# Linelance_Schematic_page3.net
KiCad netlist of a schematic drawn in Altium Designer
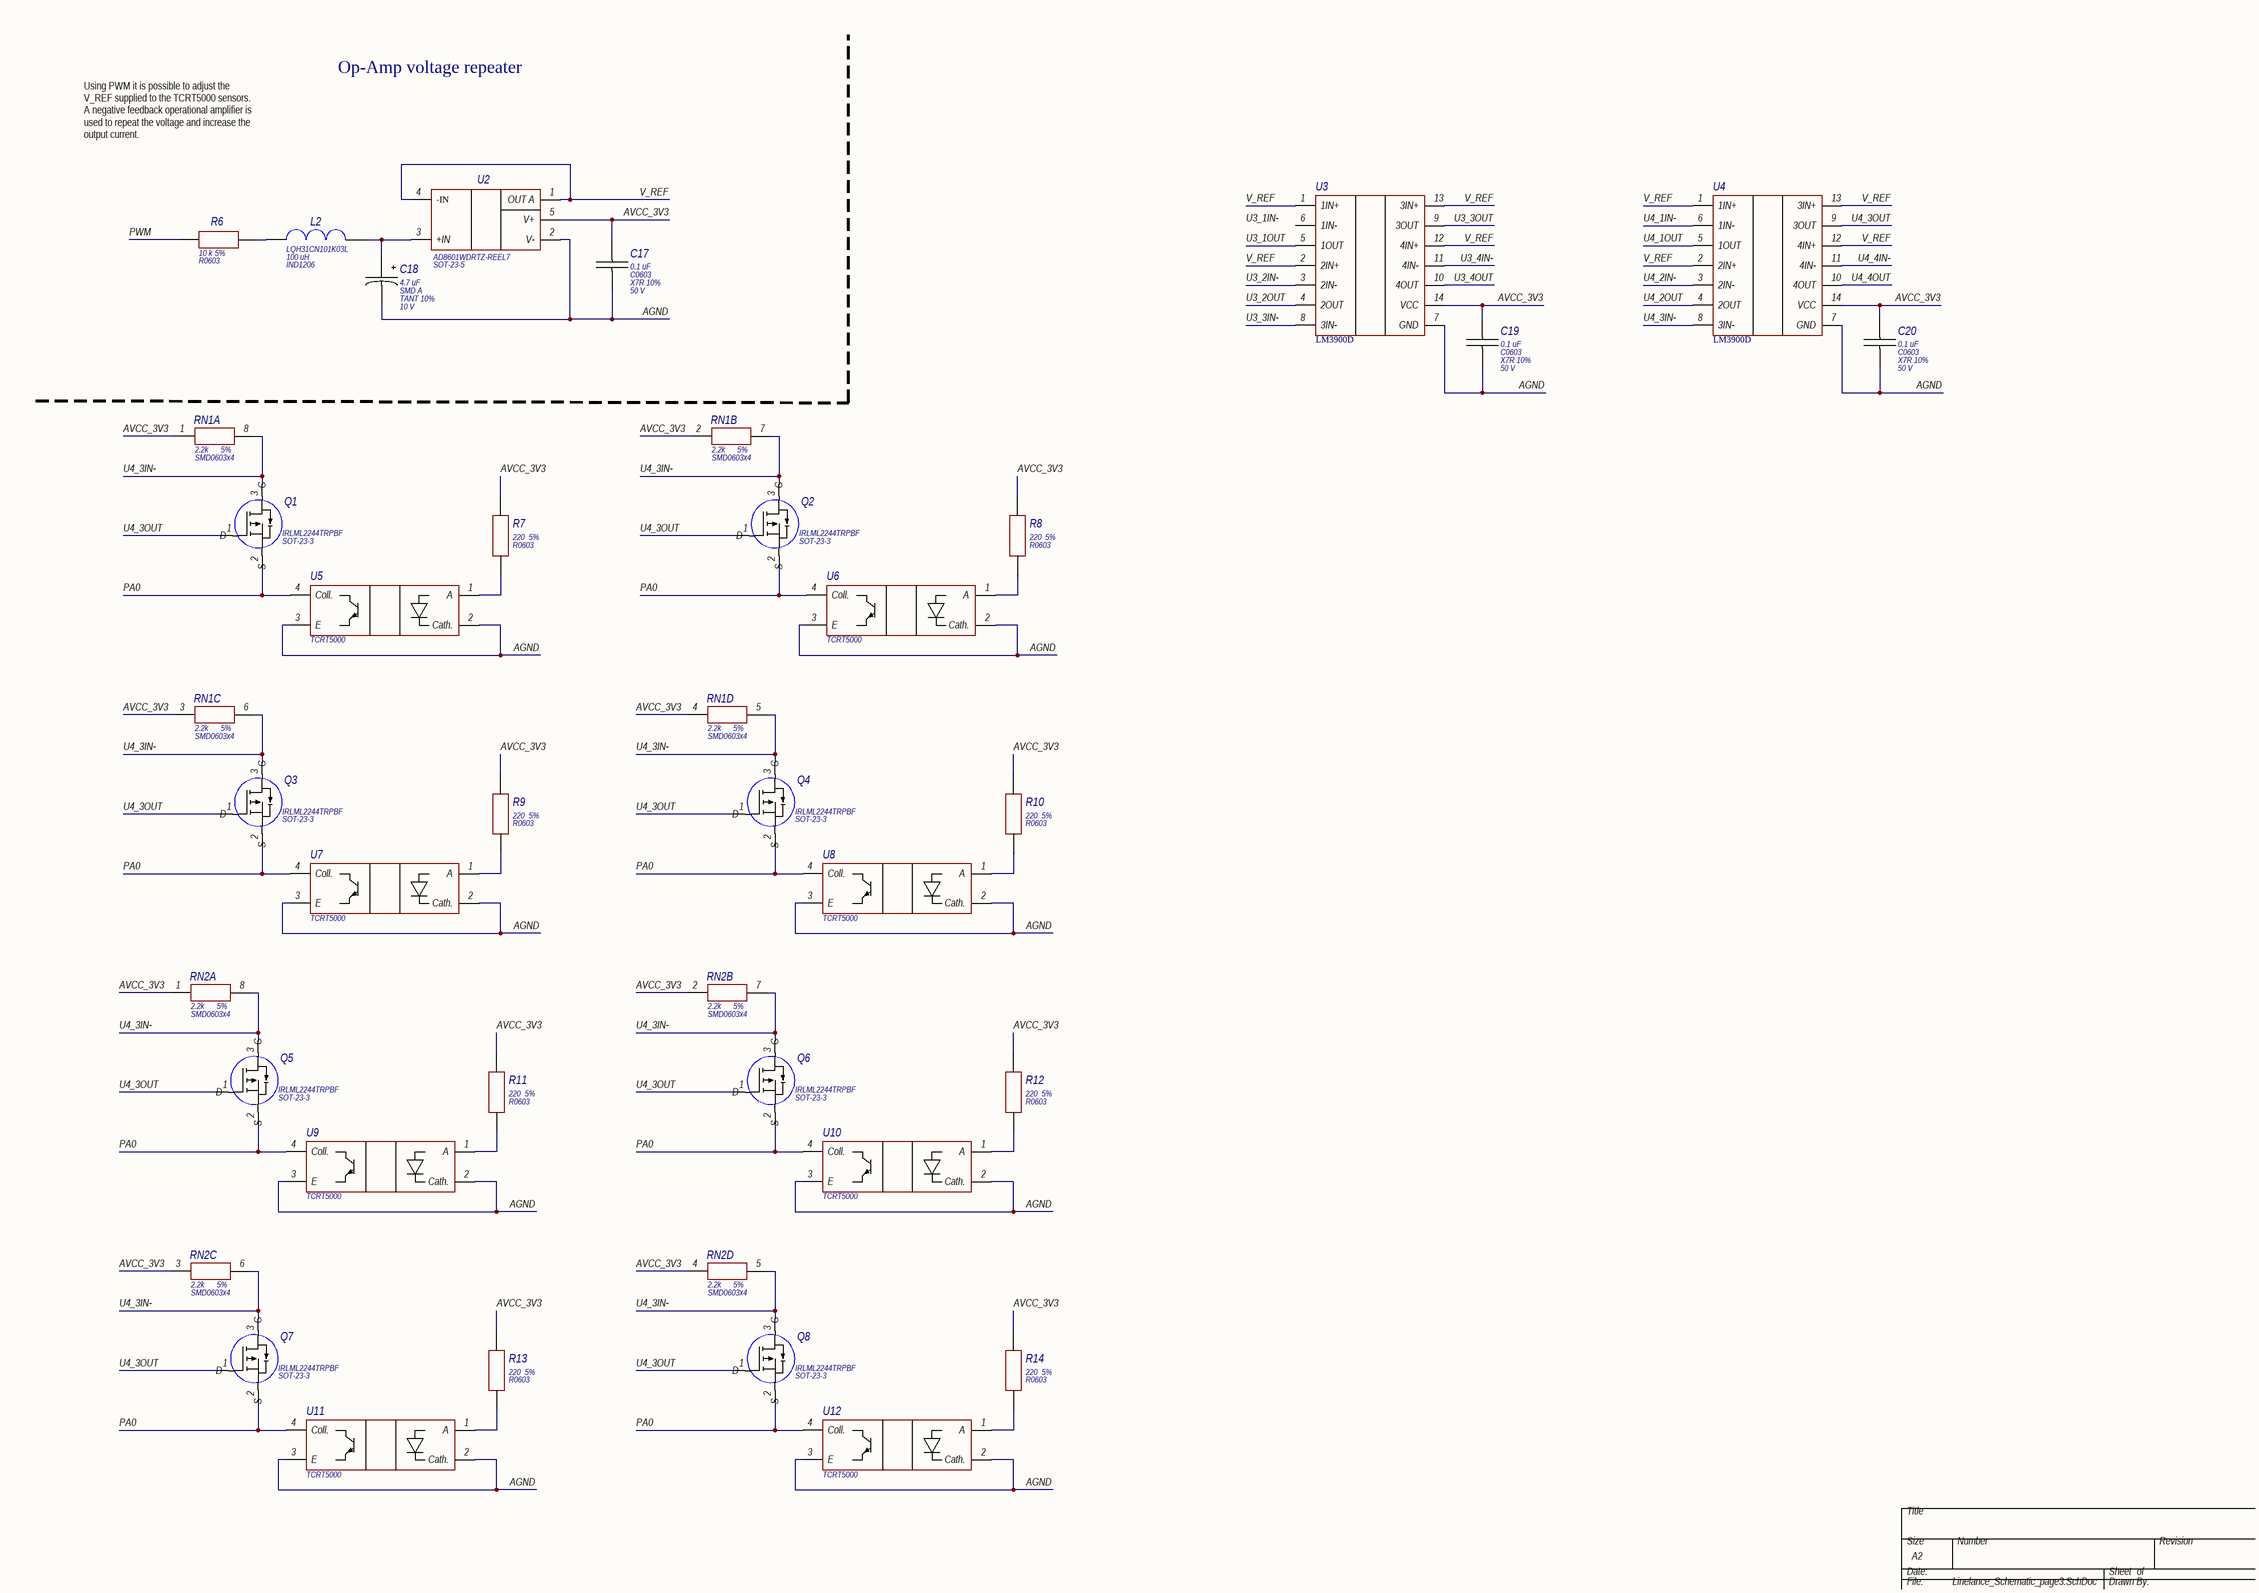
[diagram p0: Linelance_Schematic_page3.SchDoc]

(export (version "E")
  (design (tool "Eeschema 10.0.6"))
  (components
    (comp (ref "C17")
      (value "0.1 uF")
      (footprint "C0603")
      (fields
        (field (name "CASE") "C0603")
        (field (name "MANUFACTURER") "Murata Manufacturing")
        (field (name "MODEL") "X7R 10%")
        (field (name "VOLTAGE") "50 V")
      )
      (libsource (lib "Linelance_lib") (part "Capasitor_ceramic"))
    )
    (comp (ref "C18")
      (value "4.7 uF")
      (footprint "TANT-A")
      (fields
        (field (name "CASE") "SMD A")
        (field (name "MANUFACTURER") "China")
        (field (name "MODEL") "TANT 10%")
        (field (name "VOLTAGE") "10 V")
      )
      (libsource (lib "Linelance_lib") (part "Capasitor_tantalum"))
    )
    (comp (ref "C19")
      (value "0.1 uF")
      (footprint "C0603")
      (fields
        (field (name "CASE") "C0603")
        (field (name "MANUFACTURER") "Murata Manufacturing")
        (field (name "MODEL") "X7R 10%")
        (field (name "VOLTAGE") "50 V")
      )
      (libsource (lib "Linelance_lib") (part "Capasitor_ceramic"))
    )
    (comp (ref "C20")
      (value "0.1 uF")
      (footprint "C0603")
      (fields
        (field (name "CASE") "C0603")
        (field (name "MANUFACTURER") "Murata Manufacturing")
        (field (name "MODEL") "X7R 10%")
        (field (name "VOLTAGE") "50 V")
      )
      (libsource (lib "Linelance_lib") (part "Capasitor_ceramic"))
    )
    (comp (ref "L2")
      (value "100 uH")
      (footprint "IND1206")
      (fields
        (field (name "MODEL") "LQH31CN101K03L")
        (field (name "MANUFACTURER") "Murata Manufacturing")
        (field (name "CASE") "IND1206")
      )
      (libsource (lib "Linelance_lib") (part "Inductivity"))
    )
    (comp (ref "Q1")
      (value "IRLML2244TRPBF")
      (footprint "SOT-23-3")
      (description "MOSFET P-CH 20V 4.3A SOT23")
      (fields (field (name "CASE") "SOT-23-3") (field (name "MODEL") "IRLML2244TRPBF"))
      (libsource (lib "Linelance_lib") (part "IRLML2244TRPBF"))
    )
    (comp (ref "Q2")
      (value "IRLML2244TRPBF")
      (footprint "SOT-23-3")
      (description "MOSFET P-CH 20V 4.3A SOT23")
      (fields (field (name "CASE") "SOT-23-3") (field (name "MODEL") "IRLML2244TRPBF"))
      (libsource (lib "Linelance_lib") (part "IRLML2244TRPBF"))
    )
    (comp (ref "Q3")
      (value "IRLML2244TRPBF")
      (footprint "SOT-23-3")
      (description "MOSFET P-CH 20V 4.3A SOT23")
      (fields (field (name "CASE") "SOT-23-3") (field (name "MODEL") "IRLML2244TRPBF"))
      (libsource (lib "Linelance_lib") (part "IRLML2244TRPBF"))
    )
    (comp (ref "Q4")
      (value "IRLML2244TRPBF")
      (footprint "SOT-23-3")
      (description "MOSFET P-CH 20V 4.3A SOT23")
      (fields (field (name "CASE") "SOT-23-3") (field (name "MODEL") "IRLML2244TRPBF"))
      (libsource (lib "Linelance_lib") (part "IRLML2244TRPBF"))
    )
    (comp (ref "Q5")
      (value "IRLML2244TRPBF")
      (footprint "SOT-23-3")
      (description "MOSFET P-CH 20V 4.3A SOT23")
      (fields (field (name "CASE") "SOT-23-3") (field (name "MODEL") "IRLML2244TRPBF"))
      (libsource (lib "Linelance_lib") (part "IRLML2244TRPBF"))
    )
    (comp (ref "Q6")
      (value "IRLML2244TRPBF")
      (footprint "SOT-23-3")
      (description "MOSFET P-CH 20V 4.3A SOT23")
      (fields (field (name "CASE") "SOT-23-3") (field (name "MODEL") "IRLML2244TRPBF"))
      (libsource (lib "Linelance_lib") (part "IRLML2244TRPBF"))
    )
    (comp (ref "Q7")
      (value "IRLML2244TRPBF")
      (footprint "SOT-23-3")
      (description "MOSFET P-CH 20V 4.3A SOT23")
      (fields (field (name "CASE") "SOT-23-3") (field (name "MODEL") "IRLML2244TRPBF"))
      (libsource (lib "Linelance_lib") (part "IRLML2244TRPBF"))
    )
    (comp (ref "Q8")
      (value "IRLML2244TRPBF")
      (footprint "SOT-23-3")
      (description "MOSFET P-CH 20V 4.3A SOT23")
      (fields (field (name "CASE") "SOT-23-3") (field (name "MODEL") "IRLML2244TRPBF"))
      (libsource (lib "Linelance_lib") (part "IRLML2244TRPBF"))
    )
    (comp (ref "R6")
      (value "10 k")
      (footprint "R0603")
      (description "Rext.")
      (fields (field (name "MODEL") "5%") (field (name "CASE") "R0603"))
      (libsource (lib "") (part "Resistor_1"))
    )
    (comp (ref "R7")
      (value "220")
      (footprint "R0603")
      (description "Rext.")
      (fields (field (name "MODEL") "5%") (field (name "CASE") "R0603"))
      (libsource (lib "Linelance_lib") (part "Resistor"))
    )
    (comp (ref "R8")
      (value "220")
      (footprint "R0603")
      (description "Rext.")
      (fields (field (name "MODEL") "5%") (field (name "CASE") "R0603"))
      (libsource (lib "Linelance_lib") (part "Resistor"))
    )
    (comp (ref "R9")
      (value "220")
      (footprint "R0603")
      (description "Rext.")
      (fields (field (name "MODEL") "5%") (field (name "CASE") "R0603"))
      (libsource (lib "Linelance_lib") (part "Resistor"))
    )
    (comp (ref "R10")
      (value "220")
      (footprint "R0603")
      (description "Rext.")
      (fields (field (name "MODEL") "5%") (field (name "CASE") "R0603"))
      (libsource (lib "Linelance_lib") (part "Resistor"))
    )
    (comp (ref "R11")
      (value "220")
      (footprint "R0603")
      (description "Rext.")
      (fields (field (name "MODEL") "5%") (field (name "CASE") "R0603"))
      (libsource (lib "Linelance_lib") (part "Resistor"))
    )
    (comp (ref "R12")
      (value "220")
      (footprint "R0603")
      (description "Rext.")
      (fields (field (name "MODEL") "5%") (field (name "CASE") "R0603"))
      (libsource (lib "Linelance_lib") (part "Resistor"))
    )
    (comp (ref "R13")
      (value "220")
      (footprint "R0603")
      (description "Rext.")
      (fields (field (name "MODEL") "5%") (field (name "CASE") "R0603"))
      (libsource (lib "Linelance_lib") (part "Resistor"))
    )
    (comp (ref "R14")
      (value "220")
      (footprint "R0603")
      (description "Rext.")
      (fields (field (name "MODEL") "5%") (field (name "CASE") "R0603"))
      (libsource (lib "Linelance_lib") (part "Resistor"))
    )
    (comp (ref "RN1")
      (value "2.2k")
      (footprint "RN_YC164-JR-072K2L")
      (fields
        (field (name "MODEL") "5%")
        (field (name "CASE") "SMD0603x4")
        (field (name "MANUFACTURER") "Bourns")
      )
      (libsource (lib "Linelance_lib") (part "Resistor Network"))
    )
    (comp (ref "RN2")
      (value "2.2k")
      (footprint "RN_YC164-JR-072K2L")
      (fields
        (field (name "MODEL") "5%")
        (field (name "CASE") "SMD0603x4")
        (field (name "MANUFACTURER") "Bourns")
      )
      (libsource (lib "Linelance_lib") (part "Resistor Network"))
    )
    (comp (ref "U2")
      (value "AD8601WDRTZ-REEL7")
      (footprint "SOT-23-5")
      (description "IC OPAMP GP 1 CIRCUIT SOT23-5")
      (fields
        (field (name "MODEL") "AD8601WDRTZ-REEL7")
        (field (name "MANUFACTURER") "Analog Devices Inc.")
        (field (name "CASE") "SOT-23-5")
      )
      (libsource (lib "Linelance_lib") (part "AD8601"))
    )
    (comp (ref "U3")
      (value "LM3900D")
      (footprint "SOIC-14")
      (description "IC OPAMP GP 4 CIRCUIT 14SOIC")
      (fields (field (name "MANUFACTURER") "Texas Instruments"))
      (libsource (lib "Linelance_lib") (part "LM3900"))
    )
    (comp (ref "U4")
      (value "LM3900D")
      (footprint "SOIC-14")
      (description "IC OPAMP GP 4 CIRCUIT 14SOIC")
      (fields (field (name "MANUFACTURER") "Texas Instruments"))
      (libsource (lib "Linelance_lib") (part "LM3900"))
    )
    (comp (ref "U5")
      (value "TCRT5000")
      (footprint "TCRT5000")
      (description "SENSOR OPTO TRANS 15MM REFL PCB")
      (fields
        (field (name "MODEL") "TCRT5000")
        (field (name "MANUFACTURER") "Vishay Semiconductor Opto Division")
      )
      (libsource (lib "Linelance_lib") (part "TCRT5000"))
    )
    (comp (ref "U6")
      (value "TCRT5000")
      (footprint "TCRT5000")
      (description "SENSOR OPTO TRANS 15MM REFL PCB")
      (fields
        (field (name "MODEL") "TCRT5000")
        (field (name "MANUFACTURER") "Vishay Semiconductor Opto Division")
      )
      (libsource (lib "Linelance_lib") (part "TCRT5000"))
    )
    (comp (ref "U7")
      (value "TCRT5000")
      (footprint "TCRT5000")
      (description "SENSOR OPTO TRANS 15MM REFL PCB")
      (fields
        (field (name "MODEL") "TCRT5000")
        (field (name "MANUFACTURER") "Vishay Semiconductor Opto Division")
      )
      (libsource (lib "Linelance_lib") (part "TCRT5000"))
    )
    (comp (ref "U8")
      (value "TCRT5000")
      (footprint "TCRT5000")
      (description "SENSOR OPTO TRANS 15MM REFL PCB")
      (fields
        (field (name "MODEL") "TCRT5000")
        (field (name "MANUFACTURER") "Vishay Semiconductor Opto Division")
      )
      (libsource (lib "Linelance_lib") (part "TCRT5000"))
    )
    (comp (ref "U9")
      (value "TCRT5000")
      (footprint "TCRT5000")
      (description "SENSOR OPTO TRANS 15MM REFL PCB")
      (fields
        (field (name "MODEL") "TCRT5000")
        (field (name "MANUFACTURER") "Vishay Semiconductor Opto Division")
      )
      (libsource (lib "Linelance_lib") (part "TCRT5000"))
    )
    (comp (ref "U10")
      (value "TCRT5000")
      (footprint "TCRT5000")
      (description "SENSOR OPTO TRANS 15MM REFL PCB")
      (fields
        (field (name "MODEL") "TCRT5000")
        (field (name "MANUFACTURER") "Vishay Semiconductor Opto Division")
      )
      (libsource (lib "Linelance_lib") (part "TCRT5000"))
    )
    (comp (ref "U11")
      (value "TCRT5000")
      (footprint "TCRT5000")
      (description "SENSOR OPTO TRANS 15MM REFL PCB")
      (fields
        (field (name "MODEL") "TCRT5000")
        (field (name "MANUFACTURER") "Vishay Semiconductor Opto Division")
      )
      (libsource (lib "Linelance_lib") (part "TCRT5000"))
    )
    (comp (ref "U12")
      (value "TCRT5000")
      (footprint "TCRT5000")
      (description "SENSOR OPTO TRANS 15MM REFL PCB")
      (fields
        (field (name "MODEL") "TCRT5000")
        (field (name "MANUFACTURER") "Vishay Semiconductor Opto Division")
      )
      (libsource (lib "Linelance_lib") (part "TCRT5000"))
    )
  )
  (nets
    (net (code "1") (name "/AGND") (class "Default")
      (node (ref "C17") (pin "2") (pintype "passive"))
      (node (ref "C18") (pin "2") (pintype "passive"))
      (node (ref "C19") (pin "2") (pintype "passive"))
      (node (ref "C20") (pin "2") (pintype "passive"))
      (node (ref "U10") (pin "2") (pinfunction "Cath._2") (pintype "passive"))
      (node (ref "U10") (pin "3") (pinfunction "E_3") (pintype "passive"))
      (node (ref "U11") (pin "2") (pinfunction "Cath._2") (pintype "passive"))
      (node (ref "U11") (pin "3") (pinfunction "E_3") (pintype "passive"))
      (node (ref "U12") (pin "2") (pinfunction "Cath._2") (pintype "passive"))
      (node (ref "U12") (pin "3") (pinfunction "E_3") (pintype "passive"))
      (node (ref "U2") (pin "2") (pinfunction "V-_2") (pintype "passive"))
      (node (ref "U3") (pin "7") (pinfunction "GND_7") (pintype "passive"))
      (node (ref "U4") (pin "7") (pinfunction "GND_7") (pintype "passive"))
      (node (ref "U5") (pin "2") (pinfunction "Cath._2") (pintype "passive"))
      (node (ref "U5") (pin "3") (pinfunction "E_3") (pintype "passive"))
      (node (ref "U6") (pin "2") (pinfunction "Cath._2") (pintype "passive"))
      (node (ref "U6") (pin "3") (pinfunction "E_3") (pintype "passive"))
      (node (ref "U7") (pin "2") (pinfunction "Cath._2") (pintype "passive"))
      (node (ref "U7") (pin "3") (pinfunction "E_3") (pintype "passive"))
      (node (ref "U8") (pin "2") (pinfunction "Cath._2") (pintype "passive"))
      (node (ref "U8") (pin "3") (pinfunction "E_3") (pintype "passive"))
      (node (ref "U9") (pin "2") (pinfunction "Cath._2") (pintype "passive"))
      (node (ref "U9") (pin "3") (pinfunction "E_3") (pintype "passive"))
    )
    (net (code "2") (name "/AVCC_3V3") (class "Default")
      (node (ref "C17") (pin "1") (pintype "passive"))
      (node (ref "C19") (pin "1") (pintype "passive"))
      (node (ref "C20") (pin "1") (pintype "passive"))
      (node (ref "R10") (pin "2") (pintype "passive"))
      (node (ref "R11") (pin "2") (pintype "passive"))
      (node (ref "R12") (pin "2") (pintype "passive"))
      (node (ref "R13") (pin "2") (pintype "passive"))
      (node (ref "R14") (pin "2") (pintype "passive"))
      (node (ref "R7") (pin "2") (pintype "passive"))
      (node (ref "R8") (pin "2") (pintype "passive"))
      (node (ref "R9") (pin "2") (pintype "passive"))
      (node (ref "RN1") (pin "1") (pintype "passive"))
      (node (ref "RN1") (pin "2") (pintype "passive"))
      (node (ref "RN1") (pin "3") (pintype "passive"))
      (node (ref "RN1") (pin "4") (pintype "passive"))
      (node (ref "RN2") (pin "1") (pintype "passive"))
      (node (ref "RN2") (pin "2") (pintype "passive"))
      (node (ref "RN2") (pin "3") (pintype "passive"))
      (node (ref "RN2") (pin "4") (pintype "passive"))
      (node (ref "U2") (pin "5") (pinfunction "V+_5") (pintype "passive"))
      (node (ref "U3") (pin "14") (pinfunction "VCC_14") (pintype "passive"))
      (node (ref "U4") (pin "14") (pinfunction "VCC_14") (pintype "passive"))
    )
    (net (code "3") (name "/PA0") (class "Default")
      (node (ref "Q1") (pin "2") (pinfunction "S_2") (pintype "passive"))
      (node (ref "Q2") (pin "2") (pinfunction "S_2") (pintype "passive"))
      (node (ref "Q3") (pin "2") (pinfunction "S_2") (pintype "passive"))
      (node (ref "Q4") (pin "2") (pinfunction "S_2") (pintype "passive"))
      (node (ref "Q5") (pin "2") (pinfunction "S_2") (pintype "passive"))
      (node (ref "Q6") (pin "2") (pinfunction "S_2") (pintype "passive"))
      (node (ref "Q7") (pin "2") (pinfunction "S_2") (pintype "passive"))
      (node (ref "Q8") (pin "2") (pinfunction "S_2") (pintype "passive"))
      (node (ref "U10") (pin "4") (pinfunction "Coll._4") (pintype "passive"))
      (node (ref "U11") (pin "4") (pinfunction "Coll._4") (pintype "passive"))
      (node (ref "U12") (pin "4") (pinfunction "Coll._4") (pintype "passive"))
      (node (ref "U5") (pin "4") (pinfunction "Coll._4") (pintype "passive"))
      (node (ref "U6") (pin "4") (pinfunction "Coll._4") (pintype "passive"))
      (node (ref "U7") (pin "4") (pinfunction "Coll._4") (pintype "passive"))
      (node (ref "U8") (pin "4") (pinfunction "Coll._4") (pintype "passive"))
      (node (ref "U9") (pin "4") (pinfunction "Coll._4") (pintype "passive"))
    )
    (net (code "4") (name "/PWM") (class "Default") (node (ref "R6") (pin "1") (pintype "passive")))
    (net (code "6") (name "/U3_1OUT") (class "Default")
      (node (ref "U3") (pin "5") (pinfunction "1OUT_5") (pintype "passive"))
    )
    (net (code "7") (name "/U3_2IN-") (class "Default")
      (node (ref "U3") (pin "3") (pinfunction "2IN-_3") (pintype "passive"))
    )
    (net (code "8") (name "/U3_2OUT") (class "Default")
      (node (ref "U3") (pin "4") (pinfunction "2OUT_4") (pintype "passive"))
    )
    (net (code "9") (name "/U3_3IN-") (class "Default")
      (node (ref "U3") (pin "8") (pinfunction "3IN-_8") (pintype "passive"))
    )
    (net (code "10") (name "/U3_3OUT") (class "Default")
      (node (ref "U3") (pin "9") (pinfunction "3OUT_9") (pintype "passive"))
    )
    (net (code "11") (name "/U3_4IN-") (class "Default")
      (node (ref "U3") (pin "11") (pinfunction "4IN-_11") (pintype "passive"))
    )
    (net (code "12") (name "/U3_4OUT") (class "Default")
      (node (ref "U3") (pin "10") (pinfunction "4OUT_10") (pintype "passive"))
    )
    (net (code "13") (name "/U4_1IN-") (class "Default")
      (node (ref "U4") (pin "6") (pinfunction "1IN-_6") (pintype "passive"))
    )
    (net (code "14") (name "/U4_1OUT") (class "Default")
      (node (ref "U4") (pin "5") (pinfunction "1OUT_5") (pintype "passive"))
    )
    (net (code "15") (name "/U4_2IN-") (class "Default")
      (node (ref "U4") (pin "3") (pinfunction "2IN-_3") (pintype "passive"))
    )
    (net (code "16") (name "/U4_2OUT") (class "Default")
      (node (ref "U4") (pin "4") (pinfunction "2OUT_4") (pintype "passive"))
    )
    (net (code "17") (name "/U4_3IN-") (class "Default")
      (node (ref "Q1") (pin "3") (pinfunction "G_3") (pintype "passive"))
      (node (ref "Q2") (pin "3") (pinfunction "G_3") (pintype "passive"))
      (node (ref "Q3") (pin "3") (pinfunction "G_3") (pintype "passive"))
      (node (ref "Q4") (pin "3") (pinfunction "G_3") (pintype "passive"))
      (node (ref "Q5") (pin "3") (pinfunction "G_3") (pintype "passive"))
      (node (ref "Q6") (pin "3") (pinfunction "G_3") (pintype "passive"))
      (node (ref "Q7") (pin "3") (pinfunction "G_3") (pintype "passive"))
      (node (ref "Q8") (pin "3") (pinfunction "G_3") (pintype "passive"))
      (node (ref "RN1") (pin "5") (pintype "passive"))
      (node (ref "RN1") (pin "6") (pintype "passive"))
      (node (ref "RN1") (pin "7") (pintype "passive"))
      (node (ref "RN1") (pin "8") (pintype "passive"))
      (node (ref "RN2") (pin "5") (pintype "passive"))
      (node (ref "RN2") (pin "6") (pintype "passive"))
      (node (ref "RN2") (pin "7") (pintype "passive"))
      (node (ref "RN2") (pin "8") (pintype "passive"))
      (node (ref "U4") (pin "8") (pinfunction "3IN-_8") (pintype "passive"))
    )
    (net (code "18") (name "/U4_3OUT") (class "Default")
      (node (ref "Q1") (pin "1") (pinfunction "D_1") (pintype "passive"))
      (node (ref "Q2") (pin "1") (pinfunction "D_1") (pintype "passive"))
      (node (ref "Q3") (pin "1") (pinfunction "D_1") (pintype "passive"))
      (node (ref "Q4") (pin "1") (pinfunction "D_1") (pintype "passive"))
      (node (ref "Q5") (pin "1") (pinfunction "D_1") (pintype "passive"))
      (node (ref "Q6") (pin "1") (pinfunction "D_1") (pintype "passive"))
      (node (ref "Q7") (pin "1") (pinfunction "D_1") (pintype "passive"))
      (node (ref "Q8") (pin "1") (pinfunction "D_1") (pintype "passive"))
      (node (ref "U4") (pin "9") (pinfunction "3OUT_9") (pintype "passive"))
    )
    (net (code "19") (name "/U4_4IN-") (class "Default")
      (node (ref "U4") (pin "11") (pinfunction "4IN-_11") (pintype "passive"))
    )
    (net (code "20") (name "/U4_4OUT") (class "Default")
      (node (ref "U4") (pin "10") (pinfunction "4OUT_10") (pintype "passive"))
    )
    (net (code "21") (name "/V_REF") (class "Default")
      (node (ref "U2") (pin "1") (pinfunction "OUT_A_1") (pintype "passive"))
      (node (ref "U2") (pin "4") (pinfunction "-IN_4") (pintype "passive"))
      (node (ref "U3") (pin "1") (pinfunction "1IN+_1") (pintype "passive"))
      (node (ref "U3") (pin "12") (pinfunction "4IN+_12") (pintype "passive"))
      (node (ref "U3") (pin "13") (pinfunction "3IN+_13") (pintype "passive"))
      (node (ref "U3") (pin "2") (pinfunction "2IN+_2") (pintype "passive"))
      (node (ref "U4") (pin "1") (pinfunction "1IN+_1") (pintype "passive"))
      (node (ref "U4") (pin "12") (pinfunction "4IN+_12") (pintype "passive"))
      (node (ref "U4") (pin "13") (pinfunction "3IN+_13") (pintype "passive"))
      (node (ref "U4") (pin "2") (pinfunction "2IN+_2") (pintype "passive"))
    )
    (net (code "22") (name "Net-(L2-Pad1)") (class "Default")
      (node (ref "L2") (pin "1") (pintype "passive"))
      (node (ref "R6") (pin "2") (pintype "passive"))
    )
    (net (code "23") (name "Net-(U2-+IN)") (class "Default")
      (node (ref "C18") (pin "1") (pintype "passive"))
      (node (ref "L2") (pin "2") (pintype "passive"))
      (node (ref "U2") (pin "3") (pinfunction "+IN_3") (pintype "passive"))
    )
    (net (code "24") (name "Net-(U5-A)") (class "Default")
      (node (ref "R7") (pin "1") (pintype "passive"))
      (node (ref "U5") (pin "1") (pinfunction "A_1") (pintype "passive"))
    )
    (net (code "25") (name "Net-(U6-A)") (class "Default")
      (node (ref "R8") (pin "1") (pintype "passive"))
      (node (ref "U6") (pin "1") (pinfunction "A_1") (pintype "passive"))
    )
    (net (code "26") (name "Net-(U7-A)") (class "Default")
      (node (ref "R9") (pin "1") (pintype "passive"))
      (node (ref "U7") (pin "1") (pinfunction "A_1") (pintype "passive"))
    )
    (net (code "27") (name "Net-(U8-A)") (class "Default")
      (node (ref "R10") (pin "1") (pintype "passive"))
      (node (ref "U8") (pin "1") (pinfunction "A_1") (pintype "passive"))
    )
    (net (code "28") (name "Net-(U9-A)") (class "Default")
      (node (ref "R11") (pin "1") (pintype "passive"))
      (node (ref "U9") (pin "1") (pinfunction "A_1") (pintype "passive"))
    )
    (net (code "29") (name "Net-(U10-A)") (class "Default")
      (node (ref "R12") (pin "1") (pintype "passive"))
      (node (ref "U10") (pin "1") (pinfunction "A_1") (pintype "passive"))
    )
    (net (code "30") (name "Net-(U11-A)") (class "Default")
      (node (ref "R13") (pin "1") (pintype "passive"))
      (node (ref "U11") (pin "1") (pinfunction "A_1") (pintype "passive"))
    )
    (net (code "31") (name "Net-(U12-A)") (class "Default")
      (node (ref "R14") (pin "1") (pintype "passive"))
      (node (ref "U12") (pin "1") (pinfunction "A_1") (pintype "passive"))
    )
    (net (code "32") (name "unconnected-(U3-1IN--Pad6)") (class "Default")
      (node (ref "U3") (pin "6") (pinfunction "1IN-_6") (pintype "passive"))
    )
  )
)
